# HDMI.net
KiCad netlist of a schematic drawn in Altium Designer
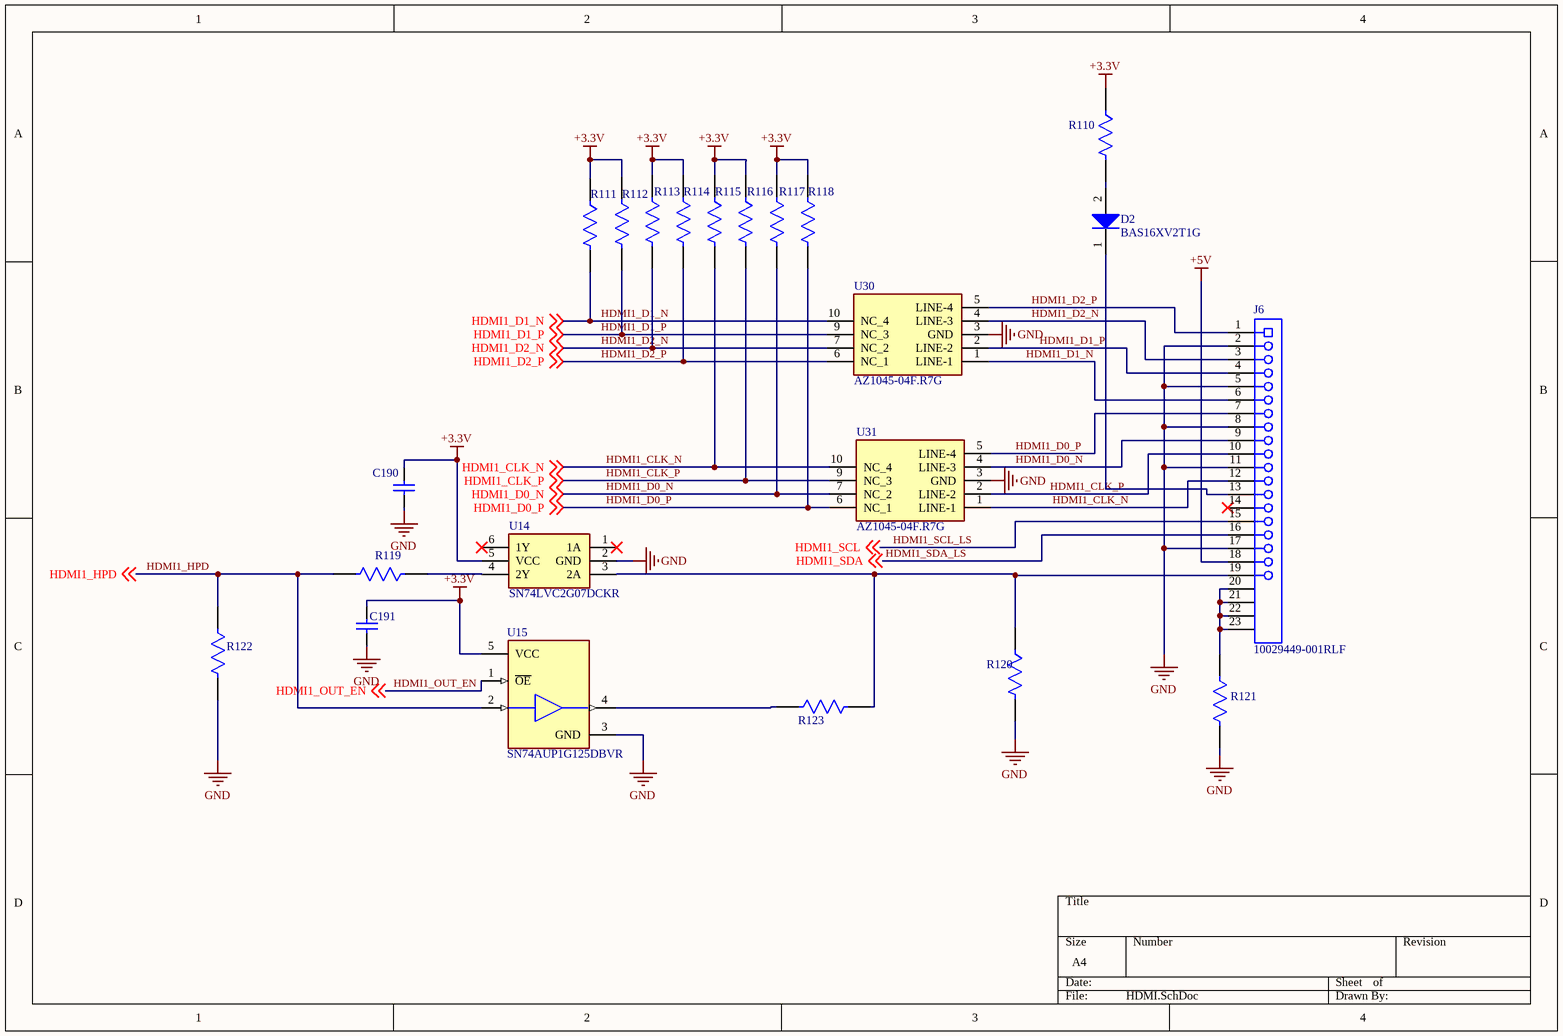
[diagram p0: HDMI.SchDoc]

(export (version "E")
  (design (tool "Eeschema 10.0.6"))
  (components
    (comp (ref "C190")
      (value "VJ0805Y152KXAAC")
      (footprint "CAPC2013X145X48NL20T23")
      (fields (field (name "MANUFACTURER") "Vitramon"))
      (libsource (lib "Altium Content Vault") (part "CAP"))
    )
    (comp (ref "C191")
      (value "VJ0805Y152KXAAC")
      (footprint "CAPC2013X145X48NL20T23")
      (fields (field (name "MANUFACTURER") "Vitramon"))
      (libsource (lib "Altium Content Vault") (part "CAP"))
    )
    (comp (ref "D2")
      (value "BAS16XV2T1G")
      (footprint "ONSC-SOD-523-2-502-01_V")
      (description "Switching Diode, 2-Pin SOD-523, Pb-Free, Tape and Reel")
      (fields (field (name "MANUFACTURER") "On Semiconductor"))
      (libsource (lib "Altium Content Vault") (part "ONSC-D-K1A2-2"))
    )
    (comp (ref "J6")
      (value "10029449-001RLF")
      (footprint "FCI-10029449-001RLF_V")
      (libsource (lib "Altium Content Vault") (part "CN-1P-F-HD19"))
    )
    (comp (ref "R110")
      (value "MCU0805MD4991BP100")
      (footprint "FP-MCU0805-MFG")
      (description "RES 1.05K OHM 0.5% 1/5W 0805")
      (fields (field (name "TOLERANCE") "0.1%"))
      (libsource (lib "Altium Content Vault") (part "1029c3af85768c4190bb7ad29bc67b5"))
    )
    (comp (ref "R111")
      (value "MCU0805MD4991BP100")
      (footprint "FP-MCU0805-MFG")
      (description "RES 1.05K OHM 0.5% 1/5W 0805")
      (fields (field (name "TOLERANCE") "0.1%"))
      (libsource (lib "Altium Content Vault") (part "1029c3af85768c4190bb7ad29bc67b5"))
    )
    (comp (ref "R112")
      (value "MCU0805MD4991BP100")
      (footprint "FP-MCU0805-MFG")
      (description "RES 1.05K OHM 0.5% 1/5W 0805")
      (fields (field (name "TOLERANCE") "0.1%"))
      (libsource (lib "Altium Content Vault") (part "1029c3af85768c4190bb7ad29bc67b5"))
    )
    (comp (ref "R113")
      (value "MCU0805MD4991BP100")
      (footprint "FP-MCU0805-MFG")
      (description "RES 1.05K OHM 0.5% 1/5W 0805")
      (fields (field (name "TOLERANCE") "0.1%"))
      (libsource (lib "Altium Content Vault") (part "1029c3af85768c4190bb7ad29bc67b5"))
    )
    (comp (ref "R114")
      (value "MCU0805MD4991BP100")
      (footprint "FP-MCU0805-MFG")
      (description "RES 1.05K OHM 0.5% 1/5W 0805")
      (fields (field (name "TOLERANCE") "0.1%"))
      (libsource (lib "Altium Content Vault") (part "1029c3af85768c4190bb7ad29bc67b5"))
    )
    (comp (ref "R115")
      (value "MCU0805MD4991BP100")
      (footprint "FP-MCU0805-MFG")
      (description "RES 1.05K OHM 0.5% 1/5W 0805")
      (fields (field (name "TOLERANCE") "0.1%"))
      (libsource (lib "Altium Content Vault") (part "1029c3af85768c4190bb7ad29bc67b5"))
    )
    (comp (ref "R116")
      (value "MCU0805MD4991BP100")
      (footprint "FP-MCU0805-MFG")
      (description "RES 1.05K OHM 0.5% 1/5W 0805")
      (fields (field (name "TOLERANCE") "0.1%"))
      (libsource (lib "Altium Content Vault") (part "1029c3af85768c4190bb7ad29bc67b5"))
    )
    (comp (ref "R117")
      (value "MCU0805MD4991BP100")
      (footprint "FP-MCU0805-MFG")
      (description "RES 1.05K OHM 0.5% 1/5W 0805")
      (fields (field (name "TOLERANCE") "0.1%"))
      (libsource (lib "Altium Content Vault") (part "1029c3af85768c4190bb7ad29bc67b5"))
    )
    (comp (ref "R118")
      (value "MCU0805MD4991BP100")
      (footprint "FP-MCU0805-MFG")
      (description "RES 1.05K OHM 0.5% 1/5W 0805")
      (fields (field (name "TOLERANCE") "0.1%"))
      (libsource (lib "Altium Content Vault") (part "1029c3af85768c4190bb7ad29bc67b5"))
    )
    (comp (ref "R119")
      (value "MCU0805MD4991BP100")
      (footprint "FP-MCU0805-MFG")
      (description "RES 1.05K OHM 0.5% 1/5W 0805")
      (fields (field (name "TOLERANCE") "0.1%"))
      (libsource (lib "Altium Content Vault") (part "1029c3af85768c4190bb7ad29bc67b5"))
    )
    (comp (ref "R120")
      (value "MCU0805MD4991BP100")
      (footprint "FP-MCU0805-MFG")
      (description "RES 1.05K OHM 0.5% 1/5W 0805")
      (fields (field (name "TOLERANCE") "0.1%"))
      (libsource (lib "Altium Content Vault") (part "1029c3af85768c4190bb7ad29bc67b5"))
    )
    (comp (ref "R121")
      (value "MCU0805MD4991BP100")
      (footprint "FP-MCU0805-MFG")
      (description "RES 1.05K OHM 0.5% 1/5W 0805")
      (fields (field (name "TOLERANCE") "0.1%"))
      (libsource (lib "Altium Content Vault") (part "1029c3af85768c4190bb7ad29bc67b5"))
    )
    (comp (ref "R122")
      (value "MCU0805MD4991BP100")
      (footprint "FP-MCU0805-MFG")
      (description "RES 1.05K OHM 0.5% 1/5W 0805")
      (fields (field (name "TOLERANCE") "0.1%"))
      (libsource (lib "Altium Content Vault") (part "1029c3af85768c4190bb7ad29bc67b5"))
    )
    (comp (ref "R123")
      (value "MCU0805MD4991BP100")
      (footprint "FP-MCU0805-MFG")
      (description "RES 1.05K OHM 0.5% 1/5W 0805")
      (fields (field (name "TOLERANCE") "0.1%"))
      (libsource (lib "Altium Content Vault") (part "1029c3af85768c4190bb7ad29bc67b5"))
    )
    (comp (ref "U14")
      (value "SN74LVC2G07DCKR")
      (footprint "SamacSys:SOT65P210X110-6N")
      (description "Integrated Circuit")
      (fields (field (name "MOUSER PART NUMBER") "595-SN74LVC2G07DCKR"))
      (libsource (lib "*") (part "SN74LVC2G07DCKR"))
    )
    (comp (ref "U15")
      (value "SN74AUP1G125DBVR")
      (footprint "FP-DBV0005A-IPC_C")
      (description "IC BUF NON-INVERT 3.6V SOT23-5")
      (libsource (lib "Altium Content Vault") (part "f838dcef8304eb4f5f138df0c0d49ae"))
    )
    (comp (ref "U30")
      (value "AZ1045-04F.R7G")
      (footprint "SamacSys:AZ104504FR7G")
      (description "Diode ESD (Uni-directional)")
      (libsource (lib "*") (part "AZ1045-04F.R7G"))
    )
    (comp (ref "U31")
      (value "AZ1045-04F.R7G")
      (footprint "SamacSys:AZ104504FR7G")
      (description "Diode ESD (Uni-directional)")
      (libsource (lib "*") (part "AZ1045-04F.R7G"))
    )
  )
  (nets
    (net (code "1") (name "+3.3V") (class "Default")
      (node (ref "C190") (pin "2") (pinfunction "2_2") (pintype "passive"))
      (node (ref "C191") (pin "2") (pinfunction "2_2") (pintype "passive"))
      (node (ref "R110") (pin "1") (pinfunction "1_1") (pintype "passive"))
      (node (ref "R111") (pin "1") (pinfunction "1_1") (pintype "passive"))
      (node (ref "R112") (pin "1") (pinfunction "1_1") (pintype "passive"))
      (node (ref "R113") (pin "1") (pinfunction "1_1") (pintype "passive"))
      (node (ref "R114") (pin "1") (pinfunction "1_1") (pintype "passive"))
      (node (ref "R115") (pin "1") (pinfunction "1_1") (pintype "passive"))
      (node (ref "R116") (pin "1") (pinfunction "1_1") (pintype "passive"))
      (node (ref "R117") (pin "1") (pinfunction "1_1") (pintype "passive"))
      (node (ref "R118") (pin "1") (pinfunction "1_1") (pintype "passive"))
      (node (ref "U14") (pin "5") (pinfunction "VCC_5") (pintype "passive"))
      (node (ref "U15") (pin "5") (pinfunction "VCC_5") (pintype "power_in"))
    )
    (net (code "2") (name "+5V") (class "Default")
      (node (ref "J6") (pin "18") (pinfunction "18_18") (pintype "passive"))
    )
    (net (code "3") (name "GND") (class "Default")
      (node (ref "C190") (pin "1") (pinfunction "1_1") (pintype "passive"))
      (node (ref "C191") (pin "1") (pinfunction "1_1") (pintype "passive"))
      (node (ref "J6") (pin "11") (pinfunction "11_11") (pintype "passive"))
      (node (ref "J6") (pin "17") (pinfunction "17_17") (pintype "passive"))
      (node (ref "J6") (pin "2") (pinfunction "2_2") (pintype "passive"))
      (node (ref "J6") (pin "5") (pinfunction "5_5") (pintype "passive"))
      (node (ref "J6") (pin "8") (pinfunction "8_8") (pintype "passive"))
      (node (ref "R120") (pin "2") (pinfunction "2_2") (pintype "passive"))
      (node (ref "R121") (pin "2") (pinfunction "2_2") (pintype "passive"))
      (node (ref "R122") (pin "2") (pinfunction "2_2") (pintype "passive"))
      (node (ref "U14") (pin "2") (pinfunction "GND_2") (pintype "passive"))
      (node (ref "U15") (pin "3") (pinfunction "GND_3") (pintype "power_in"))
      (node (ref "U30") (pin "3") (pinfunction "GND_3") (pintype "passive"))
      (node (ref "U31") (pin "3") (pinfunction "GND_3") (pintype "passive"))
    )
    (net (code "4") (name "HDMI1_CLK_N") (class "Default")
      (node (ref "J6") (pin "12") (pinfunction "12_12") (pintype "passive"))
      (node (ref "R115") (pin "2") (pinfunction "2_2") (pintype "passive"))
      (node (ref "U31") (pin "1") (pinfunction "LINE-1_1") (pintype "passive"))
      (node (ref "U31") (pin "10") (pinfunction "NC_4_10") (pintype "passive"))
    )
    (net (code "5") (name "HDMI1_CLK_P") (class "Default")
      (node (ref "J6") (pin "10") (pinfunction "10_10") (pintype "passive"))
      (node (ref "R116") (pin "2") (pinfunction "2_2") (pintype "passive"))
      (node (ref "U31") (pin "2") (pinfunction "LINE-2_2") (pintype "passive"))
      (node (ref "U31") (pin "9") (pinfunction "NC_3_9") (pintype "passive"))
    )
    (net (code "6") (name "HDMI1_D0_N") (class "Default")
      (node (ref "J6") (pin "9") (pinfunction "9_9") (pintype "passive"))
      (node (ref "R117") (pin "2") (pinfunction "2_2") (pintype "passive"))
      (node (ref "U31") (pin "4") (pinfunction "LINE-3_4") (pintype "passive"))
      (node (ref "U31") (pin "7") (pinfunction "NC_2_7") (pintype "passive"))
    )
    (net (code "7") (name "HDMI1_D0_P") (class "Default")
      (node (ref "J6") (pin "7") (pinfunction "7_7") (pintype "passive"))
      (node (ref "R118") (pin "2") (pinfunction "2_2") (pintype "passive"))
      (node (ref "U31") (pin "5") (pinfunction "LINE-4_5") (pintype "passive"))
      (node (ref "U31") (pin "6") (pinfunction "NC_1_6") (pintype "passive"))
    )
    (net (code "8") (name "HDMI1_D1_N") (class "Default")
      (node (ref "J6") (pin "6") (pinfunction "6_6") (pintype "passive"))
      (node (ref "R111") (pin "2") (pinfunction "2_2") (pintype "passive"))
      (node (ref "U30") (pin "1") (pinfunction "LINE-1_1") (pintype "passive"))
      (node (ref "U30") (pin "10") (pinfunction "NC_4_10") (pintype "passive"))
    )
    (net (code "9") (name "HDMI1_D1_P") (class "Default")
      (node (ref "J6") (pin "4") (pinfunction "4_4") (pintype "passive"))
      (node (ref "R112") (pin "2") (pinfunction "2_2") (pintype "passive"))
      (node (ref "U30") (pin "2") (pinfunction "LINE-2_2") (pintype "passive"))
      (node (ref "U30") (pin "9") (pinfunction "NC_3_9") (pintype "passive"))
    )
    (net (code "10") (name "HDMI1_D2_N") (class "Default")
      (node (ref "J6") (pin "3") (pinfunction "3_3") (pintype "passive"))
      (node (ref "R113") (pin "2") (pinfunction "2_2") (pintype "passive"))
      (node (ref "U30") (pin "4") (pinfunction "LINE-3_4") (pintype "passive"))
      (node (ref "U30") (pin "7") (pinfunction "NC_2_7") (pintype "passive"))
    )
    (net (code "11") (name "HDMI1_D2_P") (class "Default")
      (node (ref "J6") (pin "1") (pinfunction "1_1") (pintype "passive"))
      (node (ref "R114") (pin "2") (pinfunction "2_2") (pintype "passive"))
      (node (ref "U30") (pin "5") (pinfunction "LINE-4_5") (pintype "passive"))
      (node (ref "U30") (pin "6") (pinfunction "NC_1_6") (pintype "passive"))
    )
    (net (code "12") (name "HDMI1_HPD") (class "Default")
      (node (ref "R119") (pin "2") (pinfunction "2_2") (pintype "passive"))
      (node (ref "R122") (pin "1") (pinfunction "1_1") (pintype "passive"))
      (node (ref "U15") (pin "2") (pinfunction "A_2") (pintype "input"))
    )
    (net (code "13") (name "HDMI1_OUT_EN") (class "Default")
      (node (ref "U15") (pin "1") (pinfunction "~{OE}_1") (pintype "input"))
    )
    (net (code "14") (name "HDMI1_SCL") (class "Default")
      (node (ref "J6") (pin "15") (pinfunction "15_15") (pintype "passive"))
    )
    (net (code "15") (name "HDMI1_SDA") (class "Default")
      (node (ref "J6") (pin "16") (pinfunction "16_16") (pintype "passive"))
    )
    (net (code "16") (name "Net-(D2-A)") (class "Default")
      (node (ref "D2") (pin "2") (pinfunction "A_2") (pintype "passive"))
      (node (ref "R110") (pin "2") (pinfunction "2_2") (pintype "passive"))
    )
    (net (code "17") (name "Net-(D2-K)") (class "Default")
      (node (ref "D2") (pin "1") (pinfunction "K_1") (pintype "passive"))
      (node (ref "J6") (pin "13") (pinfunction "13_13") (pintype "passive"))
    )
    (net (code "18") (name "Net-(J6-SHLD1)") (class "Default")
      (node (ref "J6") (pin "20") (pinfunction "SHLD1_20") (pintype "passive"))
      (node (ref "J6") (pin "21") (pinfunction "SHLD2_21") (pintype "passive"))
      (node (ref "J6") (pin "22") (pinfunction "SHLD3_22") (pintype "passive"))
      (node (ref "J6") (pin "23") (pinfunction "SHLD4_23") (pintype "passive"))
      (node (ref "R121") (pin "1") (pinfunction "1_1") (pintype "passive"))
    )
    (net (code "19") (name "Net-(U14-2A)") (class "Default")
      (node (ref "J6") (pin "19") (pinfunction "19_19") (pintype "passive"))
      (node (ref "R120") (pin "1") (pinfunction "1_1") (pintype "passive"))
      (node (ref "R123") (pin "2") (pinfunction "2_2") (pintype "passive"))
      (node (ref "U14") (pin "3") (pinfunction "2A_3") (pintype "passive"))
    )
    (net (code "20") (name "Net-(U14-2Y)") (class "Default")
      (node (ref "R119") (pin "1") (pinfunction "1_1") (pintype "passive"))
      (node (ref "U14") (pin "4") (pinfunction "2Y_4") (pintype "passive"))
    )
    (net (code "21") (name "Net-(U15-Y)") (class "Default")
      (node (ref "R123") (pin "1") (pinfunction "1_1") (pintype "passive"))
      (node (ref "U15") (pin "4") (pinfunction "Y_4") (pintype "output"))
    )
    (net (code "22") (name "unconnected-(J6-Pad14)") (class "Default")
      (node (ref "J6") (pin "14") (pinfunction "14_14") (pintype "passive+no_connect"))
    )
    (net (code "23") (name "unconnected-(U14-1A-Pad1)") (class "Default")
      (node (ref "U14") (pin "1") (pinfunction "1A_1") (pintype "passive+no_connect"))
    )
    (net (code "24") (name "unconnected-(U14-1Y-Pad6)") (class "Default")
      (node (ref "U14") (pin "6") (pinfunction "1Y_6") (pintype "passive+no_connect"))
    )
  )
)
